# Sheet2.net
KiCad netlist of a schematic drawn in Altium Designer
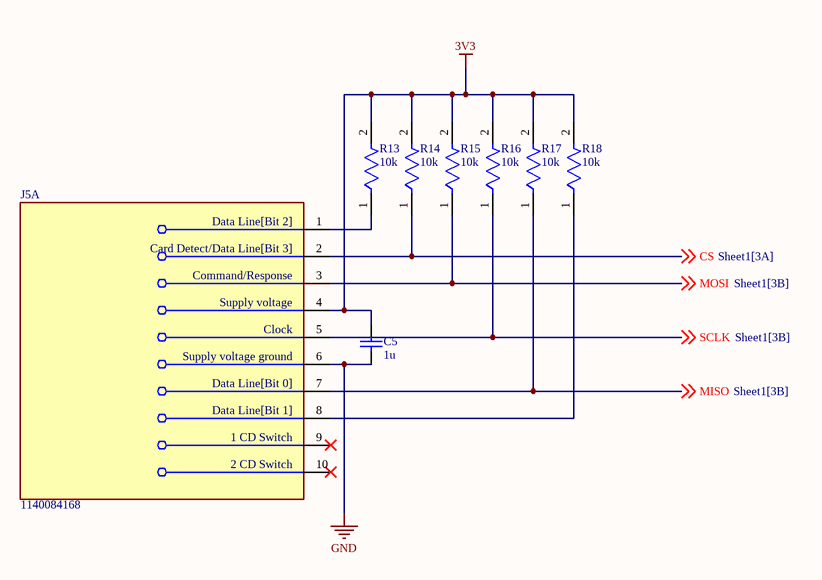
[diagram p0: Sheet2.SchDoc]

(export (version "E")
  (design (tool "Eeschema 10.0.6"))
  (components
    (comp (ref "C5")
      (value "1u")
      (footprint "CAPC3216X110X50LL20T25")
      (description "Chip Capacitor, 1 uF, +/- 10%, 50 V, -55 to 125 degC, 1206 (3216 Metric), RoHS, Tape and Reel")
      (fields (field (name "MANUFACTURER") "Kemet") (field (name "TOLERANCE") "10%"))
      (libsource (lib "Altium Content Vault") (part "CAP-NP-2"))
    )
    (comp (ref "J5")
      (value "1140084168")
      (footprint "FP-1140084168-0")
      (description "CONN MICRO SD CARD PUSH-PULL R/A")
      (libsource (lib "Altium Content Vault") (part "4825e9221753844f043cd0795554885"))
    )
    (comp (ref "R13")
      (value "10k")
      (footprint "FP-CR1206-IPC_B")
      (description "Thick Film Chip Resistors 1206 10kΩ 0.25W 5% 200ppm/°C")
      (fields (field (name "TOLERANCE") "5%"))
      (libsource (lib "Altium Content Vault") (part "1029c3af85768c4190bb7ad29bc67b5"))
    )
    (comp (ref "R14")
      (value "10k")
      (footprint "FP-CR1206-IPC_B")
      (description "Thick Film Chip Resistors 1206 10kΩ 0.25W 5% 200ppm/°C")
      (fields (field (name "TOLERANCE") "5%"))
      (libsource (lib "Altium Content Vault") (part "1029c3af85768c4190bb7ad29bc67b5"))
    )
    (comp (ref "R15")
      (value "10k")
      (footprint "FP-CR1206-IPC_B")
      (description "Thick Film Chip Resistors 1206 10kΩ 0.25W 5% 200ppm/°C")
      (fields (field (name "TOLERANCE") "5%"))
      (libsource (lib "Altium Content Vault") (part "1029c3af85768c4190bb7ad29bc67b5"))
    )
    (comp (ref "R16")
      (value "10k")
      (footprint "FP-CR1206-IPC_B")
      (description "Thick Film Chip Resistors 1206 10kΩ 0.25W 5% 200ppm/°C")
      (fields (field (name "TOLERANCE") "5%"))
      (libsource (lib "Altium Content Vault") (part "1029c3af85768c4190bb7ad29bc67b5"))
    )
    (comp (ref "R17")
      (value "10k")
      (footprint "FP-CR1206-IPC_B")
      (description "Thick Film Chip Resistors 1206 10kΩ 0.25W 5% 200ppm/°C")
      (fields (field (name "TOLERANCE") "5%"))
      (libsource (lib "Altium Content Vault") (part "1029c3af85768c4190bb7ad29bc67b5"))
    )
    (comp (ref "R18")
      (value "10k")
      (footprint "FP-CR1206-IPC_B")
      (description "Thick Film Chip Resistors 1206 10kΩ 0.25W 5% 200ppm/°C")
      (fields (field (name "TOLERANCE") "5%"))
      (libsource (lib "Altium Content Vault") (part "1029c3af85768c4190bb7ad29bc67b5"))
    )
  )
  (nets
    (net (code "1") (name "3V3") (class "Default")
      (node (ref "C5") (pin "2") (pinfunction "2_2") (pintype "passive"))
      (node (ref "J5") (pin "4") (pinfunction "Supply_voltage_4") (pintype "passive"))
      (node (ref "R13") (pin "2") (pinfunction "2_2") (pintype "passive"))
      (node (ref "R14") (pin "2") (pinfunction "2_2") (pintype "passive"))
      (node (ref "R15") (pin "2") (pinfunction "2_2") (pintype "passive"))
      (node (ref "R16") (pin "2") (pinfunction "2_2") (pintype "passive"))
      (node (ref "R17") (pin "2") (pinfunction "2_2") (pintype "passive"))
      (node (ref "R18") (pin "2") (pinfunction "2_2") (pintype "passive"))
    )
    (net (code "2") (name "CS") (class "Default")
      (node (ref "J5") (pin "2") (pinfunction "Card_Detect/Data_Line[Bit_3]_2") (pintype "passive"))
      (node (ref "R14") (pin "1") (pinfunction "1_1") (pintype "passive"))
    )
    (net (code "3") (name "GND") (class "Default")
      (node (ref "C5") (pin "1") (pinfunction "1_1") (pintype "passive"))
      (node (ref "J5") (pin "6") (pinfunction "Supply_voltage_ground_6") (pintype "passive"))
    )
    (net (code "4") (name "MISO") (class "Default")
      (node (ref "J5") (pin "7") (pinfunction "Data_Line[Bit_0]_7") (pintype "passive"))
      (node (ref "R17") (pin "1") (pinfunction "1_1") (pintype "passive"))
    )
    (net (code "5") (name "MOSI") (class "Default")
      (node (ref "J5") (pin "3") (pinfunction "Command/Response_3") (pintype "passive"))
      (node (ref "R15") (pin "1") (pinfunction "1_1") (pintype "passive"))
    )
    (net (code "6") (name "Net-(J5A-Data_Line[Bit_1])") (class "Default")
      (node (ref "J5") (pin "8") (pinfunction "Data_Line[Bit_1]_8") (pintype "passive"))
      (node (ref "R18") (pin "1") (pinfunction "1_1") (pintype "passive"))
    )
    (net (code "7") (name "Net-(J5A-Data_Line[Bit_2])") (class "Default")
      (node (ref "J5") (pin "1") (pinfunction "Data_Line[Bit_2]_1") (pintype "passive"))
      (node (ref "R13") (pin "1") (pinfunction "1_1") (pintype "passive"))
    )
    (net (code "8") (name "SCLK") (class "Default")
      (node (ref "J5") (pin "5") (pinfunction "Clock_5") (pintype "passive"))
      (node (ref "R16") (pin "1") (pinfunction "1_1") (pintype "passive"))
    )
    (net (code "9") (name "unconnected-(J5A-1_CD_Switch-Pad9)") (class "Default")
      (node (ref "J5") (pin "9") (pinfunction "1_CD_Switch_9") (pintype "passive+no_connect"))
    )
    (net (code "10") (name "unconnected-(J5A-2_CD_Switch-Pad10)") (class "Default")
      (node (ref "J5") (pin "10") (pinfunction "2_CD_Switch_10") (pintype "passive+no_connect"))
    )
  )
)
